# SparkFun_9DoF_ISM330DHCX-MMC5983MA.net
KiCad netlist of a schematic drawn in EAGLE
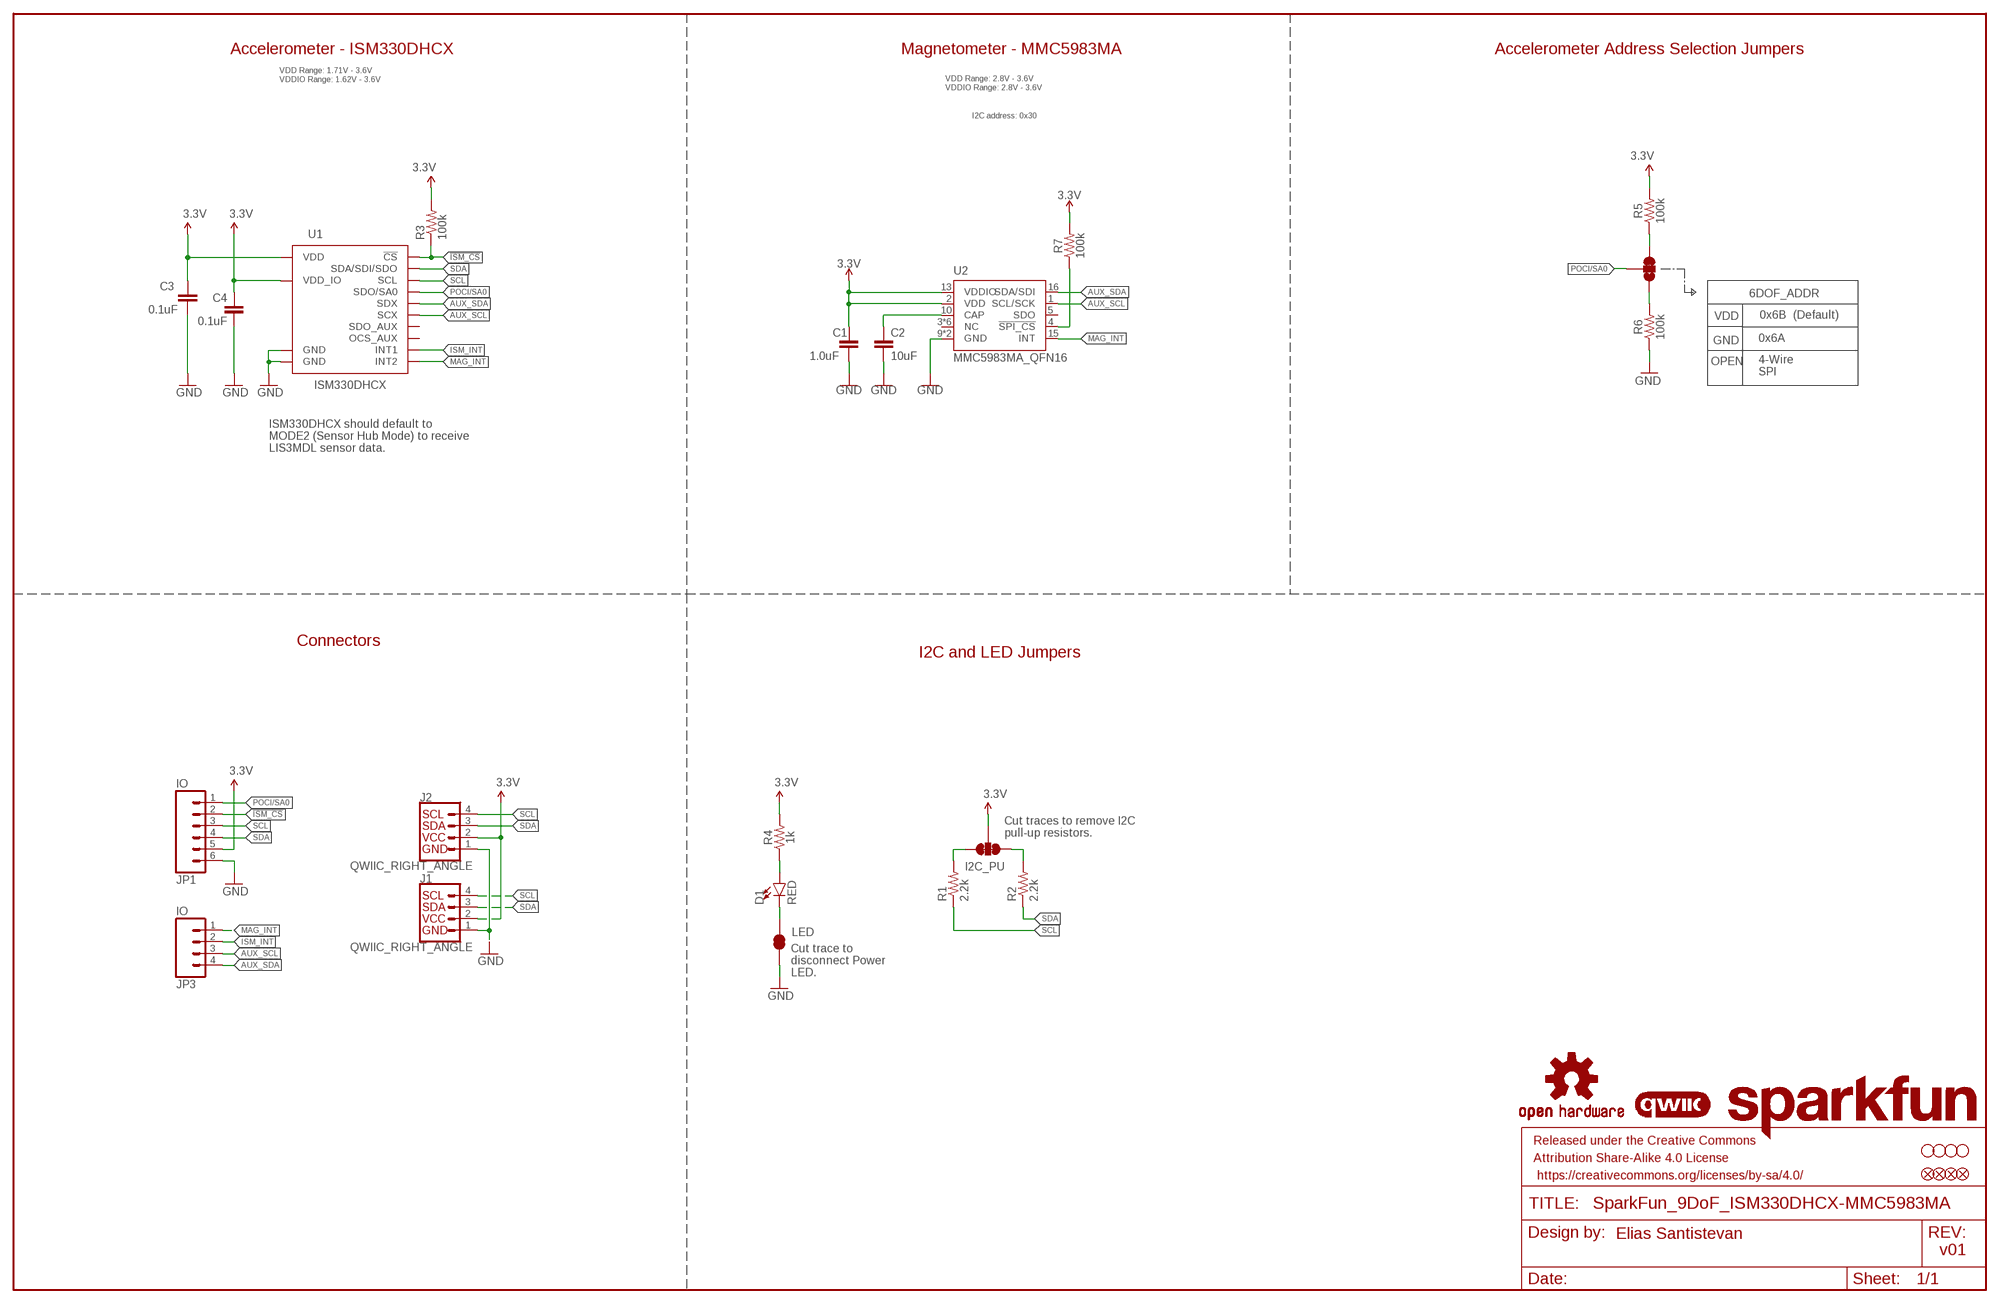
[diagram p0: schematic, sheet 1]

(export (version "E")
  (design (tool "Eeschema 10.0.6"))
  (components
    (comp (ref "6DOF_ADDR")
      (value "JUMPER-SMT_3_1-NC_TRACE_SILK")
      (footprint "eagle-import:SMT-JUMPER_3_1-NC_TRACE_SILK")
      (libsource (lib "eagle-import") (part "JUMPER-SMT_3_1-NC_TRACE_SILK"))
    )
    (comp (ref "C1")
      (value "1.0uF")
      (footprint "eagle-import:0603")
      (libsource (lib "eagle-import") (part "1.0UF-0603-16V-10%"))
    )
    (comp (ref "C2")
      (value "10uF")
      (footprint "eagle-import:0603")
      (libsource (lib "eagle-import") (part "10UF-0603-6.3V-20%"))
    )
    (comp (ref "C3")
      (value "0.1uF")
      (footprint "eagle-import:0603")
      (libsource (lib "eagle-import") (part "0.1UF-0603-25V-(+80/-20%)"))
    )
    (comp (ref "C4")
      (value "0.1uF")
      (footprint "eagle-import:0603")
      (libsource (lib "eagle-import") (part "0.1UF-0603-25V-(+80/-20%)"))
    )
    (comp (ref "D1")
      (value "RED")
      (footprint "eagle-import:LED-0603")
      (libsource (lib "eagle-import") (part "LED-RED0603"))
    )
    (comp (ref "FD1")
      (value "FIDUCIALUFIDUCIAL")
      (footprint "eagle-import:FIDUCIAL-MICRO")
      (libsource (lib "eagle-import") (part "FIDUCIALUFIDUCIAL"))
    )
    (comp (ref "FD2")
      (value "FIDUCIALUFIDUCIAL")
      (footprint "eagle-import:FIDUCIAL-MICRO")
      (libsource (lib "eagle-import") (part "FIDUCIALUFIDUCIAL"))
    )
    (comp (ref "FID1")
      (value "FIDUCIALUFIDUCIAL")
      (footprint "eagle-import:FIDUCIAL-MICRO")
      (libsource (lib "eagle-import") (part "FIDUCIALUFIDUCIAL"))
    )
    (comp (ref "FID2")
      (value "FIDUCIALUFIDUCIAL")
      (footprint "eagle-import:FIDUCIAL-MICRO")
      (libsource (lib "eagle-import") (part "FIDUCIALUFIDUCIAL"))
    )
    (comp (ref "FRAME2")
      (value "FRAME-LEDGER")
      (footprint "eagle-import:CREATIVE_COMMONS")
      (libsource (lib "eagle-import") (part "FRAME-LEDGER"))
    )
    (comp (ref "I2C_PU")
      (value "S_MODE")
      (footprint "eagle-import:SMT-JUMPER_3_2-NC_TRACE_SILK")
      (libsource (lib "eagle-import") (part "JUMPER-SMT_3_2-NC_TRACE_SILK"))
    )
    (comp (ref "J1")
      (value "QWIIC_RIGHT_ANGLE")
      (footprint "eagle-import:JST04_1MM_RA")
      (libsource (lib "eagle-import") (part "QWIIC_CONNECTORJS-1MM"))
    )
    (comp (ref "J2")
      (value "QWIIC_RIGHT_ANGLE")
      (footprint "eagle-import:JST04_1MM_RA")
      (libsource (lib "eagle-import") (part "QWIIC_CONNECTORJS-1MM"))
    )
    (comp (ref "JP1")
      (value "IO")
      (footprint "eagle-import:1X06_NO_SILK")
      (libsource (lib "eagle-import") (part "CONN_06NO_SILK_NO_POP"))
    )
    (comp (ref "JP3")
      (value "IO")
      (footprint "eagle-import:1X04_NO_SILK")
      (libsource (lib "eagle-import") (part "CONN_041X04_NO_SILK_NO_POP"))
    )
    (comp (ref "LED")
      (value "JUMPER-SMT_2_NC_TRACE_SILK")
      (footprint "eagle-import:SMT-JUMPER_2_NC_TRACE_SILK")
      (libsource (lib "eagle-import") (part "JUMPER-SMT_2_NC_TRACE_SILK"))
    )
    (comp (ref "LOGO1")
      (value "QWIIC_LOGO_4MM")
      (footprint "eagle-import:QWIIC_4MM")
      (libsource (lib "eagle-import") (part "QWIIC_LOGO_4MM"))
    )
    (comp (ref "LOGO2")
      (value "OSHW-LOGOMINI")
      (footprint "eagle-import:OSHW-LOGO-MINI")
      (libsource (lib "eagle-import") (part "OSHW-LOGOMINI"))
    )
    (comp (ref "LOGO3")
      (value "SFE_LOGO_NAME.1_INCH")
      (footprint "eagle-import:SFE_LOGO_NAME_.1")
      (libsource (lib "eagle-import") (part "SFE_LOGO_NAME.1_INCH"))
    )
    (comp (ref "R1")
      (value "2.2k")
      (footprint "eagle-import:0603")
      (libsource (lib "eagle-import") (part "2.2KOHM-0603-1/10W-1%"))
    )
    (comp (ref "R2")
      (value "2.2k")
      (footprint "eagle-import:0603")
      (libsource (lib "eagle-import") (part "2.2KOHM-0603-1/10W-1%"))
    )
    (comp (ref "R3")
      (value "100k")
      (footprint "eagle-import:0603")
      (libsource (lib "eagle-import") (part "100KOHM-0603-1/10W-1%"))
    )
    (comp (ref "R4")
      (value "1k")
      (footprint "eagle-import:0603")
      (libsource (lib "eagle-import") (part "1KOHM-0603-1/10W-1%"))
    )
    (comp (ref "R5")
      (value "100k")
      (footprint "eagle-import:0603")
      (libsource (lib "eagle-import") (part "100KOHM-0603-1/10W-1%"))
    )
    (comp (ref "R6")
      (value "100k")
      (footprint "eagle-import:0603")
      (libsource (lib "eagle-import") (part "100KOHM-0603-1/10W-1%"))
    )
    (comp (ref "R7")
      (value "100k")
      (footprint "eagle-import:0603")
      (libsource (lib "eagle-import") (part "100KOHM-0603-1/10W-1%"))
    )
    (comp (ref "STANDOFF1")
      (value "STAND-OFFTIGHT")
      (footprint "eagle-import:STAND-OFF-TIGHT")
      (libsource (lib "eagle-import") (part "STAND-OFFTIGHT"))
    )
    (comp (ref "STANDOFF2")
      (value "STAND-OFFTIGHT")
      (footprint "eagle-import:STAND-OFF-TIGHT")
      (libsource (lib "eagle-import") (part "STAND-OFFTIGHT"))
    )
    (comp (ref "STANDOFF3")
      (value "STAND-OFFTIGHT")
      (footprint "eagle-import:STAND-OFF-TIGHT")
      (libsource (lib "eagle-import") (part "STAND-OFFTIGHT"))
    )
    (comp (ref "STANDOFF4")
      (value "STAND-OFFTIGHT")
      (footprint "eagle-import:STAND-OFF-TIGHT")
      (libsource (lib "eagle-import") (part "STAND-OFFTIGHT"))
    )
    (comp (ref "U1")
      (value "ISM330DHCX")
      (footprint "eagle-import:LGA-14L")
      (libsource (lib "eagle-import") (part "ISM330DHCX"))
    )
    (comp (ref "U2")
      (value "MMC5983MA_QFN16")
      (footprint "eagle-import:LGA-16-3X3MM-4X4PINS")
      (libsource (lib "eagle-import") (part "MMC5983MA_QFN16"))
    )
  )
  (nets
    (net (code "1") (name "/~{ISM_CS}") (class "Default")
      (node (ref "JP1") (pin "2") (pinfunction "2_2") (pintype "passive"))
      (node (ref "R3") (pin "1") (pinfunction "1_1") (pintype "passive"))
      (node (ref "U1") (pin "P12") (pinfunction "~{CS}_P12") (pintype "bidirectional"))
    )
    (net (code "2") (name "3.3V") (class "Default")
      (node (ref "C1") (pin "1") (pinfunction "1_1") (pintype "passive"))
      (node (ref "C3") (pin "1") (pinfunction "1_1") (pintype "passive"))
      (node (ref "C4") (pin "1") (pinfunction "1_1") (pintype "passive"))
      (node (ref "I2C_PU") (pin "2") (pinfunction "2_2") (pintype "passive"))
      (node (ref "J1") (pin "2") (pinfunction "2_2") (pintype "power_in"))
      (node (ref "J2") (pin "2") (pinfunction "2_2") (pintype "power_in"))
      (node (ref "JP1") (pin "5") (pinfunction "5_5") (pintype "passive"))
      (node (ref "R3") (pin "2") (pinfunction "2_2") (pintype "passive"))
      (node (ref "R4") (pin "2") (pinfunction "2_2") (pintype "passive"))
      (node (ref "R5") (pin "2") (pinfunction "2_2") (pintype "passive"))
      (node (ref "R7") (pin "2") (pinfunction "2_2") (pintype "passive"))
      (node (ref "U1") (pin "P5") (pinfunction "VDD_IO_P5") (pintype "power_in"))
      (node (ref "U1") (pin "P8") (pinfunction "VDD_P8") (pintype "power_in"))
      (node (ref "U2") (pin "13") (pinfunction "VDDIO_13") (pintype "power_in"))
      (node (ref "U2") (pin "2") (pinfunction "VDD_2") (pintype "power_in"))
    )
    (net (code "3") (name "AUX_SCL") (class "Default")
      (node (ref "JP3") (pin "3") (pinfunction "3_3") (pintype "passive"))
      (node (ref "U1") (pin "P3") (pinfunction "SCX_P3") (pintype "bidirectional"))
      (node (ref "U2") (pin "1") (pinfunction "SCL/SCK_1") (pintype "bidirectional"))
    )
    (net (code "4") (name "AUX_SDA") (class "Default")
      (node (ref "JP3") (pin "4") (pinfunction "4_4") (pintype "passive"))
      (node (ref "U1") (pin "P2") (pinfunction "SDX_P2") (pintype "bidirectional"))
      (node (ref "U2") (pin "16") (pinfunction "SDA/SDI_16") (pintype "bidirectional"))
    )
    (net (code "5") (name "GND") (class "Default")
      (node (ref "C1") (pin "2") (pinfunction "2_2") (pintype "passive"))
      (node (ref "C2") (pin "2") (pinfunction "2_2") (pintype "passive"))
      (node (ref "C3") (pin "2") (pinfunction "2_2") (pintype "passive"))
      (node (ref "C4") (pin "2") (pinfunction "2_2") (pintype "passive"))
      (node (ref "J1") (pin "1") (pinfunction "1_1") (pintype "power_in"))
      (node (ref "J2") (pin "1") (pinfunction "1_1") (pintype "power_in"))
      (node (ref "JP1") (pin "6") (pinfunction "6_6") (pintype "passive"))
      (node (ref "LED") (pin "1") (pinfunction "1_1") (pintype "passive"))
      (node (ref "R6") (pin "1") (pinfunction "1_1") (pintype "passive"))
      (node (ref "U1") (pin "P6") (pinfunction "GND_P6") (pintype "power_in"))
      (node (ref "U1") (pin "P7") (pinfunction "GND_P7") (pintype "power_in"))
      (node (ref "U2") (pin "11") (pinfunction "GND_11") (pintype "power_in"))
      (node (ref "U2") (pin "9") (pinfunction "GND_9") (pintype "power_in"))
    )
    (net (code "6") (name "ISM_INT") (class "Default")
      (node (ref "JP3") (pin "2") (pinfunction "2_2") (pintype "passive"))
      (node (ref "U1") (pin "P4") (pinfunction "INT1_P4") (pintype "bidirectional"))
    )
    (net (code "7") (name "MAG_INT") (class "Default")
      (node (ref "JP3") (pin "1") (pinfunction "1_1") (pintype "passive"))
      (node (ref "U1") (pin "P9") (pinfunction "INT2_P9") (pintype "bidirectional"))
      (node (ref "U2") (pin "15") (pinfunction "INT_15") (pintype "output"))
    )
    (net (code "8") (name "Net-(6DOF_ADDR-Pad1)") (class "Default")
      (node (ref "6DOF_ADDR") (pin "1") (pinfunction "1_1") (pintype "passive"))
      (node (ref "R6") (pin "2") (pinfunction "2_2") (pintype "passive"))
    )
    (net (code "9") (name "Net-(6DOF_ADDR-Pad3)") (class "Default")
      (node (ref "6DOF_ADDR") (pin "3") (pinfunction "3_3") (pintype "passive"))
      (node (ref "R5") (pin "1") (pinfunction "1_1") (pintype "passive"))
    )
    (net (code "10") (name "Net-(D1-PadA)") (class "Default")
      (node (ref "D1") (pin "A") (pinfunction "A_A") (pintype "passive"))
      (node (ref "R4") (pin "1") (pinfunction "1_1") (pintype "passive"))
    )
    (net (code "11") (name "Net-(D1-PadC)") (class "Default")
      (node (ref "D1") (pin "C") (pinfunction "C_C") (pintype "passive"))
      (node (ref "LED") (pin "2") (pinfunction "2_2") (pintype "passive"))
    )
    (net (code "12") (name "Net-(I2C_PU-Pad1)") (class "Default")
      (node (ref "I2C_PU") (pin "1") (pinfunction "1_1") (pintype "passive"))
      (node (ref "R1") (pin "2") (pinfunction "2_2") (pintype "passive"))
    )
    (net (code "13") (name "Net-(I2C_PU-Pad3)") (class "Default")
      (node (ref "I2C_PU") (pin "3") (pinfunction "3_3") (pintype "passive"))
      (node (ref "R2") (pin "2") (pinfunction "2_2") (pintype "passive"))
    )
    (net (code "14") (name "Net-(U2-CAP)") (class "Default")
      (node (ref "C2") (pin "1") (pinfunction "1_1") (pintype "passive"))
      (node (ref "U2") (pin "10") (pinfunction "CAP_10") (pintype "passive"))
    )
    (net (code "15") (name "Net-(U2-~{SPI_CS})") (class "Default")
      (node (ref "R7") (pin "1") (pinfunction "1_1") (pintype "passive"))
      (node (ref "U2") (pin "4") (pinfunction "~{SPI_CS}_4") (pintype "input"))
    )
    (net (code "16") (name "POCI{slash}SA0") (class "Default")
      (node (ref "6DOF_ADDR") (pin "2") (pinfunction "2_2") (pintype "passive"))
      (node (ref "JP1") (pin "1") (pinfunction "1_1") (pintype "passive"))
      (node (ref "U1") (pin "P1") (pinfunction "SDO/SA0_P1") (pintype "bidirectional"))
    )
    (net (code "17") (name "SCL") (class "Default")
      (node (ref "J1") (pin "4") (pinfunction "4_4") (pintype "passive"))
      (node (ref "J2") (pin "4") (pinfunction "4_4") (pintype "passive"))
      (node (ref "JP1") (pin "3") (pinfunction "3_3") (pintype "passive"))
      (node (ref "R1") (pin "1") (pinfunction "1_1") (pintype "passive"))
      (node (ref "U1") (pin "P13") (pinfunction "SCL_P13") (pintype "bidirectional"))
    )
    (net (code "18") (name "SDA") (class "Default")
      (node (ref "J1") (pin "3") (pinfunction "3_3") (pintype "passive"))
      (node (ref "J2") (pin "3") (pinfunction "3_3") (pintype "passive"))
      (node (ref "JP1") (pin "4") (pinfunction "4_4") (pintype "passive"))
      (node (ref "R2") (pin "1") (pinfunction "1_1") (pintype "passive"))
      (node (ref "U1") (pin "P14") (pinfunction "SDA/SDI/SDO_P14") (pintype "bidirectional"))
    )
    (net (code "19") (name "unconnected-(U1-OCS_AUX-PadP10)") (class "Default")
      (node (ref "U1") (pin "P10") (pinfunction "OCS_AUX_P10") (pintype "bidirectional"))
    )
    (net (code "20") (name "unconnected-(U1-SDO_AUX-PadP11)") (class "Default")
      (node (ref "U1") (pin "P11") (pinfunction "SDO_AUX_P11") (pintype "bidirectional"))
    )
    (net (code "21") (name "unconnected-(U2-NC-Pad3)") (class "Default")
      (node (ref "U2") (pin "3") (pinfunction "NC_3") (pintype "no_connect"))
    )
    (net (code "22") (name "unconnected-(U2-NC-Pad6)") (class "Default")
      (node (ref "U2") (pin "6") (pinfunction "NC_6") (pintype "no_connect"))
    )
    (net (code "23") (name "unconnected-(U2-NC-Pad7)") (class "Default")
      (node (ref "U2") (pin "7") (pinfunction "NC_7") (pintype "no_connect"))
    )
    (net (code "24") (name "unconnected-(U2-NC-Pad8)") (class "Default")
      (node (ref "U2") (pin "8") (pinfunction "NC_8") (pintype "no_connect"))
    )
    (net (code "25") (name "unconnected-(U2-NC-Pad12)") (class "Default")
      (node (ref "U2") (pin "12") (pinfunction "NC_12") (pintype "no_connect"))
    )
    (net (code "26") (name "unconnected-(U2-NC-Pad14)") (class "Default")
      (node (ref "U2") (pin "14") (pinfunction "NC_14") (pintype "no_connect"))
    )
    (net (code "27") (name "unconnected-(U2-SDO-Pad5)") (class "Default")
      (node (ref "U2") (pin "5") (pinfunction "SDO_5") (pintype "output"))
    )
  )
)
